# Batt_Op_Amp.net
KiCad netlist of a schematic drawn in Altium Designer
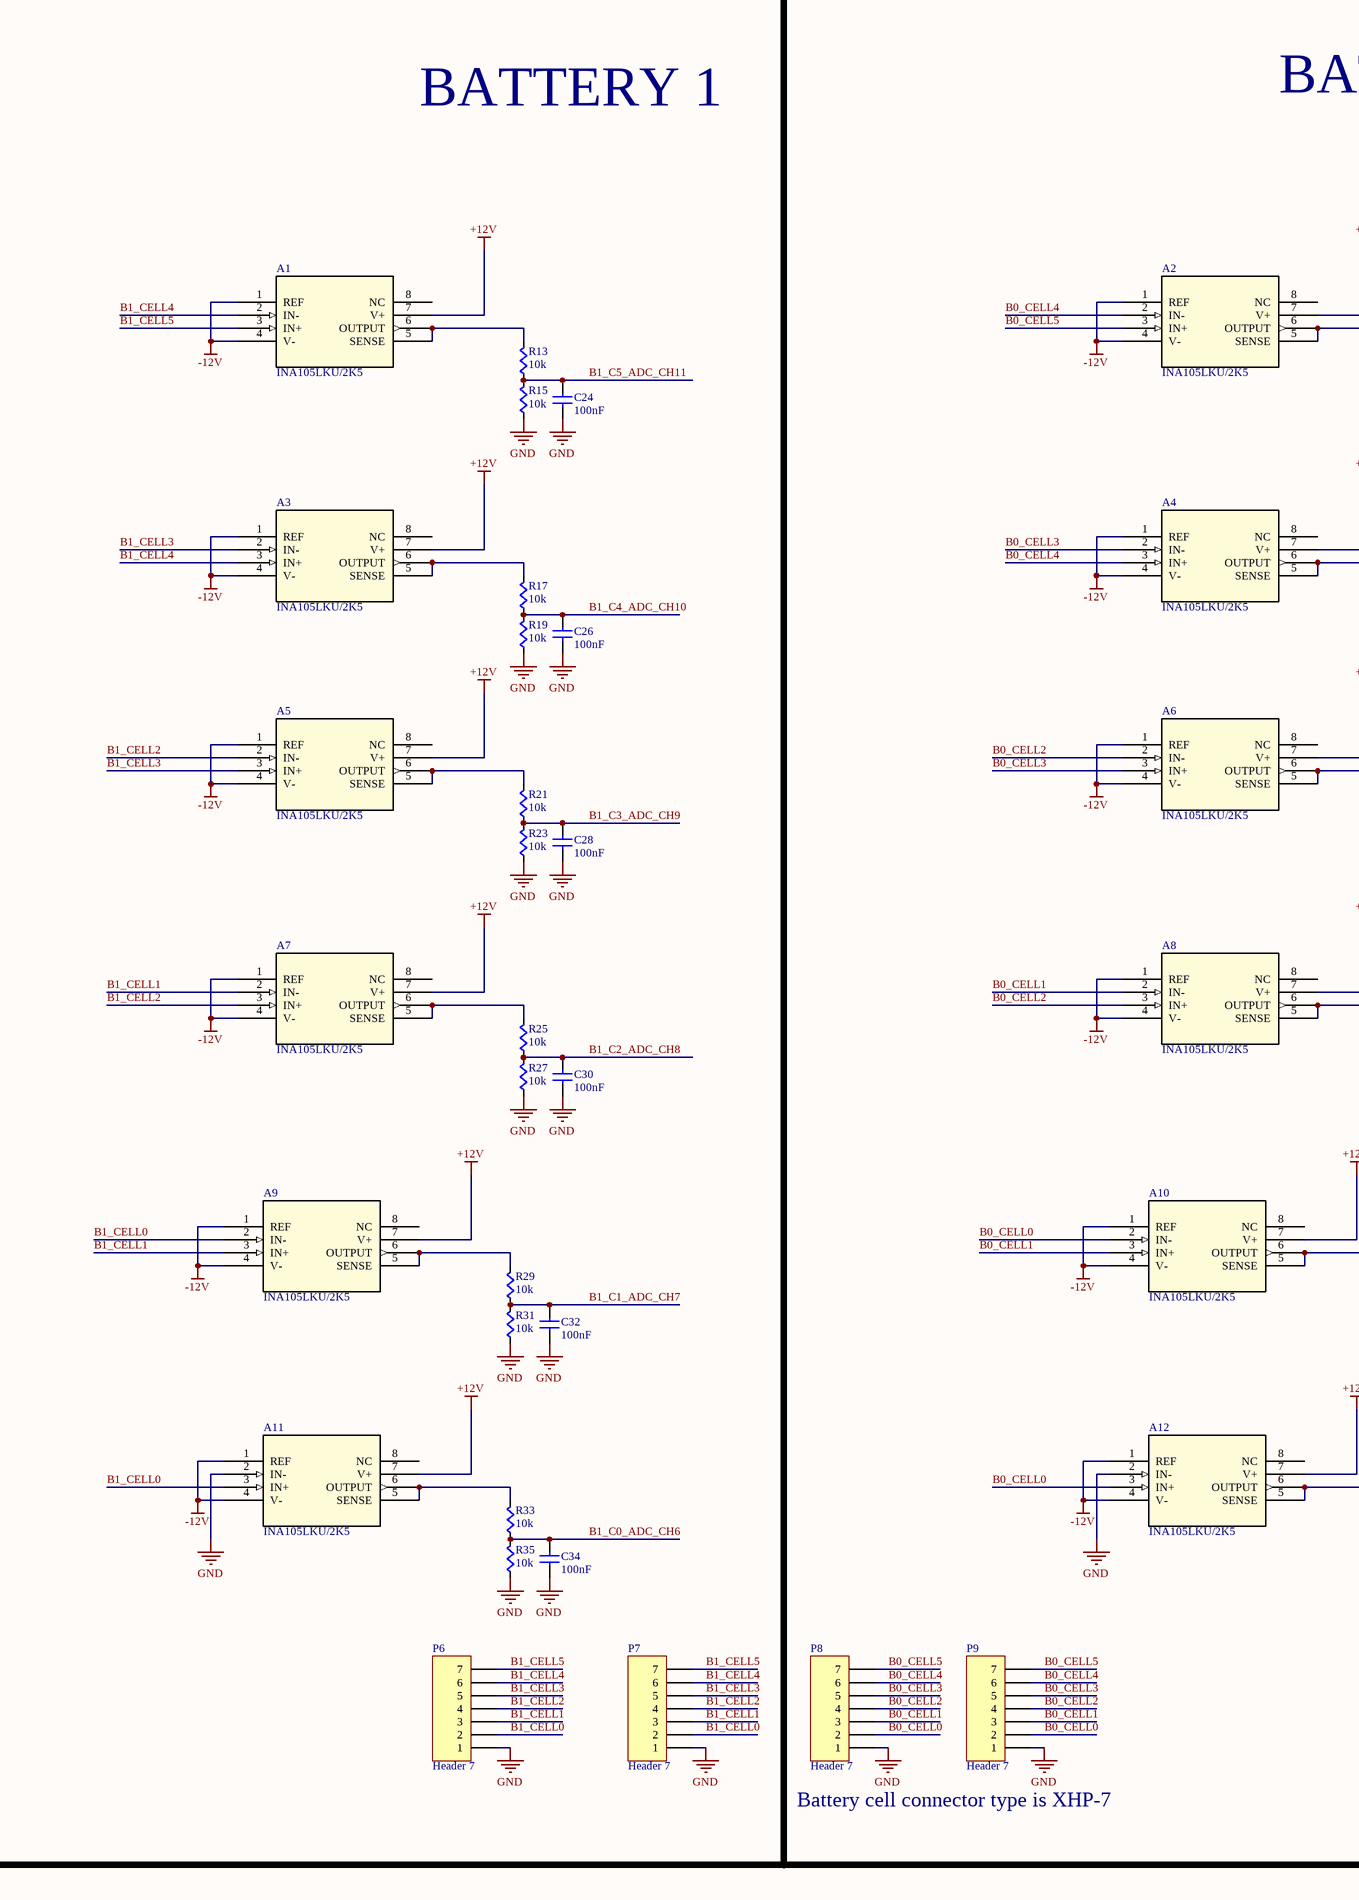
[diagram p0: Batt_Op_Amp.SchDoc, left]
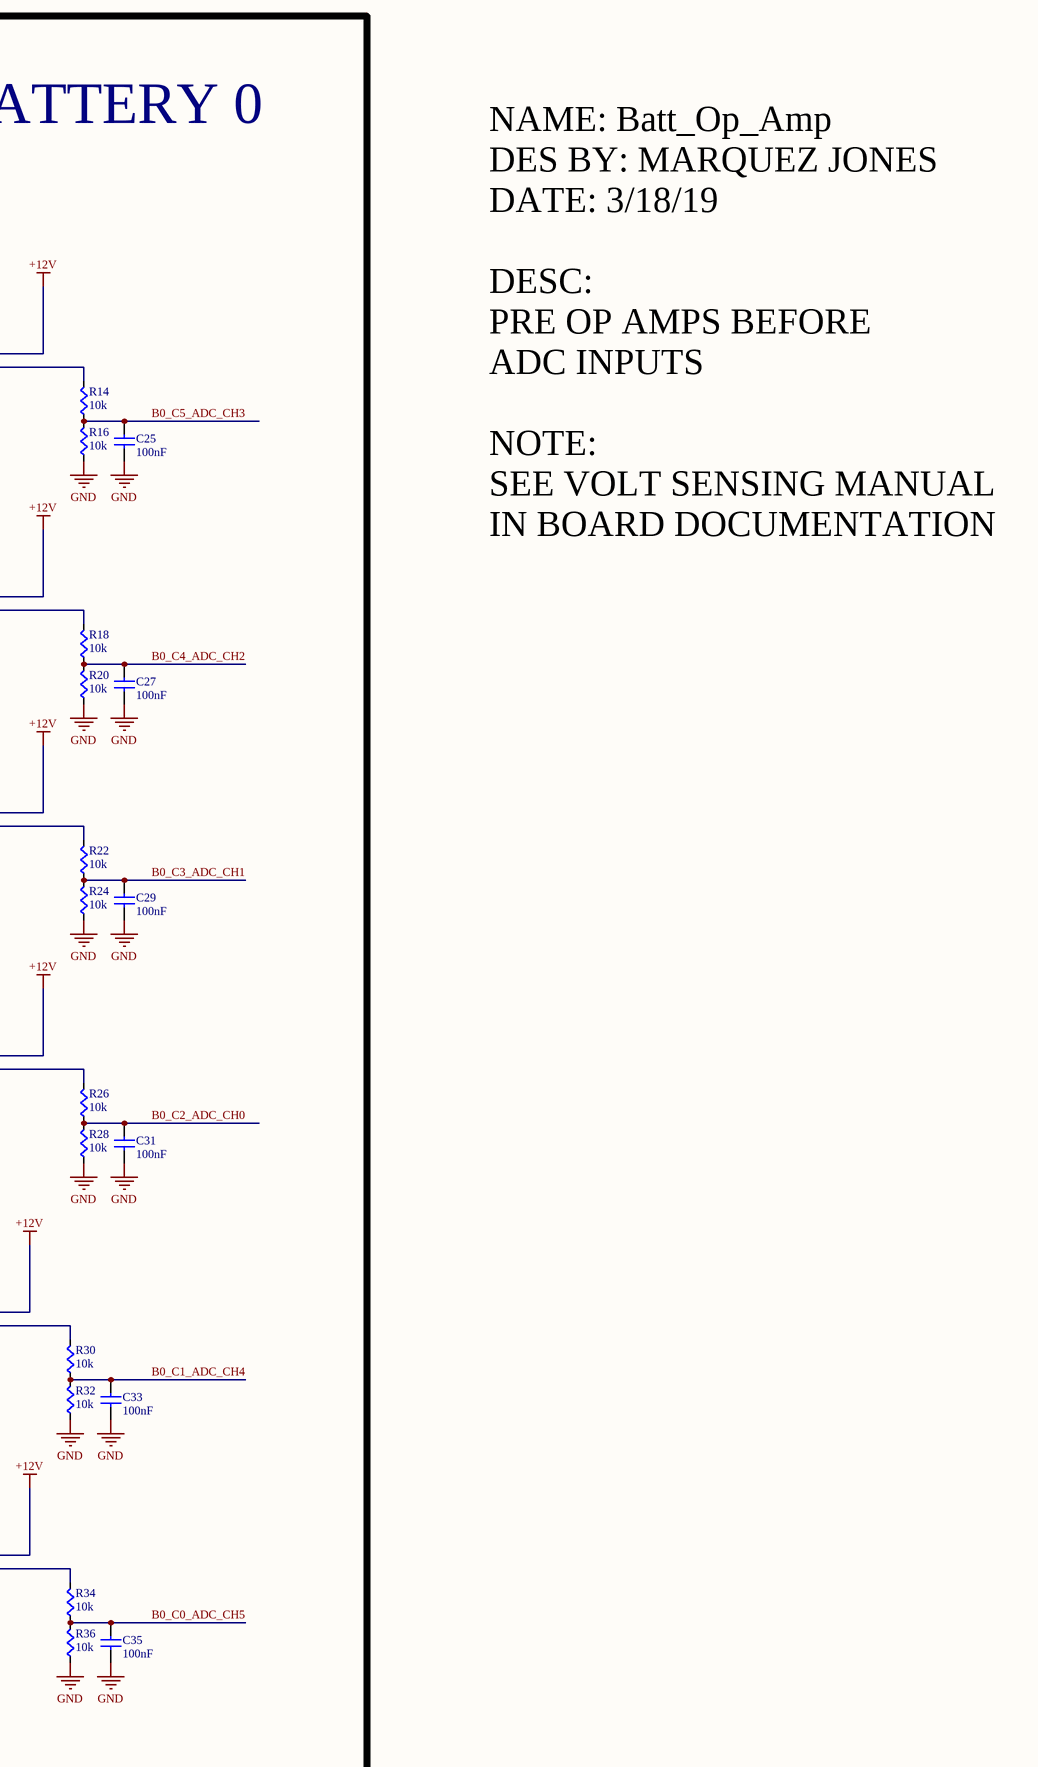
[diagram p1: Batt_Op_Amp.SchDoc, right]

(export (version "E")
  (design (tool "Eeschema 10.0.6"))
  (components
    (comp (ref "A1")
      (value "INA105LKU/2K5")
      (footprint "SOIC-8N")
      (libsource (lib "ICs") (part "INA105LKU/2K5"))
    )
    (comp (ref "A2")
      (value "INA105LKU/2K5")
      (footprint "SOIC-8N")
      (libsource (lib "ICs") (part "INA105LKU/2K5"))
    )
    (comp (ref "A3")
      (value "INA105LKU/2K5")
      (footprint "SOIC-8N")
      (libsource (lib "ICs") (part "INA105LKU/2K5"))
    )
    (comp (ref "A4")
      (value "INA105LKU/2K5")
      (footprint "SOIC-8N")
      (libsource (lib "ICs") (part "INA105LKU/2K5"))
    )
    (comp (ref "A5")
      (value "INA105LKU/2K5")
      (footprint "SOIC-8N")
      (libsource (lib "ICs") (part "INA105LKU/2K5"))
    )
    (comp (ref "A6")
      (value "INA105LKU/2K5")
      (footprint "SOIC-8N")
      (libsource (lib "ICs") (part "INA105LKU/2K5"))
    )
    (comp (ref "A7")
      (value "INA105LKU/2K5")
      (footprint "SOIC-8N")
      (libsource (lib "ICs") (part "INA105LKU/2K5"))
    )
    (comp (ref "A8")
      (value "INA105LKU/2K5")
      (footprint "SOIC-8N")
      (libsource (lib "ICs") (part "INA105LKU/2K5"))
    )
    (comp (ref "A9")
      (value "INA105LKU/2K5")
      (footprint "SOIC-8N")
      (libsource (lib "ICs") (part "INA105LKU/2K5"))
    )
    (comp (ref "A10")
      (value "INA105LKU/2K5")
      (footprint "SOIC-8N")
      (libsource (lib "ICs") (part "INA105LKU/2K5"))
    )
    (comp (ref "A11")
      (value "INA105LKU/2K5")
      (footprint "SOIC-8N")
      (libsource (lib "ICs") (part "INA105LKU/2K5"))
    )
    (comp (ref "A12")
      (value "INA105LKU/2K5")
      (footprint "SOIC-8N")
      (libsource (lib "ICs") (part "INA105LKU/2K5"))
    )
    (comp (ref "C24")
      (value "100nF")
      (footprint "CAPC0603")
      (fields (field (name "Comment") "Cap"))
      (libsource (lib "Passives") (part "Cap"))
    )
    (comp (ref "C25")
      (value "100nF")
      (footprint "CAPC0603")
      (fields (field (name "Comment") "Cap"))
      (libsource (lib "Passives") (part "Cap"))
    )
    (comp (ref "C26")
      (value "100nF")
      (footprint "CAPC0603")
      (fields (field (name "Comment") "Cap"))
      (libsource (lib "Passives") (part "Cap"))
    )
    (comp (ref "C27")
      (value "100nF")
      (footprint "CAPC0603")
      (fields (field (name "Comment") "Cap"))
      (libsource (lib "Passives") (part "Cap"))
    )
    (comp (ref "C28")
      (value "100nF")
      (footprint "CAPC0603")
      (fields (field (name "Comment") "Cap"))
      (libsource (lib "Passives") (part "Cap"))
    )
    (comp (ref "C29")
      (value "100nF")
      (footprint "CAPC0603")
      (fields (field (name "Comment") "Cap"))
      (libsource (lib "Passives") (part "Cap"))
    )
    (comp (ref "C30")
      (value "100nF")
      (footprint "CAPC0603")
      (fields (field (name "Comment") "Cap"))
      (libsource (lib "Passives") (part "Cap"))
    )
    (comp (ref "C31")
      (value "100nF")
      (footprint "CAPC0603")
      (fields (field (name "Comment") "Cap"))
      (libsource (lib "Passives") (part "Cap"))
    )
    (comp (ref "C32")
      (value "100nF")
      (footprint "CAPC0603")
      (fields (field (name "Comment") "Cap"))
      (libsource (lib "Passives") (part "Cap"))
    )
    (comp (ref "C33")
      (value "100nF")
      (footprint "CAPC0603")
      (fields (field (name "Comment") "Cap"))
      (libsource (lib "Passives") (part "Cap"))
    )
    (comp (ref "C34")
      (value "100nF")
      (footprint "CAPC0603")
      (fields (field (name "Comment") "Cap"))
      (libsource (lib "Passives") (part "Cap"))
    )
    (comp (ref "C35")
      (value "100nF")
      (footprint "CAPC0603")
      (fields (field (name "Comment") "Cap"))
      (libsource (lib "Passives") (part "Cap"))
    )
    (comp (ref "P6")
      (value "Header 7")
      (footprint "HDR1X7")
      (description "Header, 7-Pin")
      (fields (field (name "PUBLISHER") "Altium Limited"))
      (libsource (lib "Miscellaneous Connectors") (part "Header 7"))
    )
    (comp (ref "P7")
      (value "Header 7")
      (footprint "HDR1X7")
      (description "Header, 7-Pin")
      (fields (field (name "PUBLISHER") "Altium Limited"))
      (libsource (lib "Miscellaneous Connectors") (part "Header 7"))
    )
    (comp (ref "P8")
      (value "Header 7")
      (footprint "HDR1X7")
      (description "Header, 7-Pin")
      (fields (field (name "PUBLISHER") "Altium Limited"))
      (libsource (lib "Miscellaneous Connectors") (part "Header 7"))
    )
    (comp (ref "P9")
      (value "Header 7")
      (footprint "HDR1X7")
      (description "Header, 7-Pin")
      (fields (field (name "PUBLISHER") "Altium Limited"))
      (libsource (lib "Miscellaneous Connectors") (part "Header 7"))
    )
    (comp (ref "R13")
      (value "10k")
      (footprint "RES0603")
      (fields (field (name "Comment") "Res"))
      (libsource (lib "Passives") (part "Res"))
    )
    (comp (ref "R14")
      (value "10k")
      (footprint "RES0603")
      (fields (field (name "Comment") "Res"))
      (libsource (lib "Passives") (part "Res"))
    )
    (comp (ref "R15")
      (value "10k")
      (footprint "RES0603")
      (fields (field (name "Comment") "Res"))
      (libsource (lib "Passives") (part "Res"))
    )
    (comp (ref "R16")
      (value "10k")
      (footprint "RES0603")
      (fields (field (name "Comment") "Res"))
      (libsource (lib "Passives") (part "Res"))
    )
    (comp (ref "R17")
      (value "10k")
      (footprint "RES0603")
      (fields (field (name "Comment") "Res"))
      (libsource (lib "Passives") (part "Res"))
    )
    (comp (ref "R18")
      (value "10k")
      (footprint "RES0603")
      (fields (field (name "Comment") "Res"))
      (libsource (lib "Passives") (part "Res"))
    )
    (comp (ref "R19")
      (value "10k")
      (footprint "RES0603")
      (fields (field (name "Comment") "Res"))
      (libsource (lib "Passives") (part "Res"))
    )
    (comp (ref "R20")
      (value "10k")
      (footprint "RES0603")
      (fields (field (name "Comment") "Res"))
      (libsource (lib "Passives") (part "Res"))
    )
    (comp (ref "R21")
      (value "10k")
      (footprint "RES0603")
      (fields (field (name "Comment") "Res"))
      (libsource (lib "Passives") (part "Res"))
    )
    (comp (ref "R22")
      (value "10k")
      (footprint "RES0603")
      (fields (field (name "Comment") "Res"))
      (libsource (lib "Passives") (part "Res"))
    )
    (comp (ref "R23")
      (value "10k")
      (footprint "RES0603")
      (fields (field (name "Comment") "Res"))
      (libsource (lib "Passives") (part "Res"))
    )
    (comp (ref "R24")
      (value "10k")
      (footprint "RES0603")
      (fields (field (name "Comment") "Res"))
      (libsource (lib "Passives") (part "Res"))
    )
    (comp (ref "R25")
      (value "10k")
      (footprint "RES0603")
      (fields (field (name "Comment") "Res"))
      (libsource (lib "Passives") (part "Res"))
    )
    (comp (ref "R26")
      (value "10k")
      (footprint "RES0603")
      (fields (field (name "Comment") "Res"))
      (libsource (lib "Passives") (part "Res"))
    )
    (comp (ref "R27")
      (value "10k")
      (footprint "RES0603")
      (fields (field (name "Comment") "Res"))
      (libsource (lib "Passives") (part "Res"))
    )
    (comp (ref "R28")
      (value "10k")
      (footprint "RES0603")
      (fields (field (name "Comment") "Res"))
      (libsource (lib "Passives") (part "Res"))
    )
    (comp (ref "R29")
      (value "10k")
      (footprint "RES0603")
      (fields (field (name "Comment") "Res"))
      (libsource (lib "Passives") (part "Res"))
    )
    (comp (ref "R30")
      (value "10k")
      (footprint "RES0603")
      (fields (field (name "Comment") "Res"))
      (libsource (lib "Passives") (part "Res"))
    )
    (comp (ref "R31")
      (value "10k")
      (footprint "RES0603")
      (fields (field (name "Comment") "Res"))
      (libsource (lib "Passives") (part "Res"))
    )
    (comp (ref "R32")
      (value "10k")
      (footprint "RES0603")
      (fields (field (name "Comment") "Res"))
      (libsource (lib "Passives") (part "Res"))
    )
    (comp (ref "R33")
      (value "10k")
      (footprint "RES0603")
      (fields (field (name "Comment") "Res"))
      (libsource (lib "Passives") (part "Res"))
    )
    (comp (ref "R34")
      (value "10k")
      (footprint "RES0603")
      (fields (field (name "Comment") "Res"))
      (libsource (lib "Passives") (part "Res"))
    )
    (comp (ref "R35")
      (value "10k")
      (footprint "RES0603")
      (fields (field (name "Comment") "Res"))
      (libsource (lib "Passives") (part "Res"))
    )
    (comp (ref "R36")
      (value "10k")
      (footprint "RES0603")
      (fields (field (name "Comment") "Res"))
      (libsource (lib "Passives") (part "Res"))
    )
  )
  (nets
    (net (code "1") (name "+12V") (class "Default")
      (node (ref "A1") (pin "7") (pinfunction "V+_7") (pintype "power_in"))
      (node (ref "A10") (pin "7") (pinfunction "V+_7") (pintype "power_in"))
      (node (ref "A11") (pin "7") (pinfunction "V+_7") (pintype "power_in"))
      (node (ref "A12") (pin "7") (pinfunction "V+_7") (pintype "power_in"))
      (node (ref "A2") (pin "7") (pinfunction "V+_7") (pintype "power_in"))
      (node (ref "A3") (pin "7") (pinfunction "V+_7") (pintype "power_in"))
      (node (ref "A4") (pin "7") (pinfunction "V+_7") (pintype "power_in"))
      (node (ref "A5") (pin "7") (pinfunction "V+_7") (pintype "power_in"))
      (node (ref "A6") (pin "7") (pinfunction "V+_7") (pintype "power_in"))
      (node (ref "A7") (pin "7") (pinfunction "V+_7") (pintype "power_in"))
      (node (ref "A8") (pin "7") (pinfunction "V+_7") (pintype "power_in"))
      (node (ref "A9") (pin "7") (pinfunction "V+_7") (pintype "power_in"))
    )
    (net (code "2") (name "-12V") (class "Default")
      (node (ref "A1") (pin "1") (pinfunction "REF_1") (pintype "power_in"))
      (node (ref "A1") (pin "4") (pinfunction "V-_4") (pintype "power_in"))
      (node (ref "A10") (pin "1") (pinfunction "REF_1") (pintype "power_in"))
      (node (ref "A10") (pin "4") (pinfunction "V-_4") (pintype "power_in"))
      (node (ref "A11") (pin "1") (pinfunction "REF_1") (pintype "power_in"))
      (node (ref "A11") (pin "4") (pinfunction "V-_4") (pintype "power_in"))
      (node (ref "A12") (pin "1") (pinfunction "REF_1") (pintype "power_in"))
      (node (ref "A12") (pin "4") (pinfunction "V-_4") (pintype "power_in"))
      (node (ref "A2") (pin "1") (pinfunction "REF_1") (pintype "power_in"))
      (node (ref "A2") (pin "4") (pinfunction "V-_4") (pintype "power_in"))
      (node (ref "A3") (pin "1") (pinfunction "REF_1") (pintype "power_in"))
      (node (ref "A3") (pin "4") (pinfunction "V-_4") (pintype "power_in"))
      (node (ref "A4") (pin "1") (pinfunction "REF_1") (pintype "power_in"))
      (node (ref "A4") (pin "4") (pinfunction "V-_4") (pintype "power_in"))
      (node (ref "A5") (pin "1") (pinfunction "REF_1") (pintype "power_in"))
      (node (ref "A5") (pin "4") (pinfunction "V-_4") (pintype "power_in"))
      (node (ref "A6") (pin "1") (pinfunction "REF_1") (pintype "power_in"))
      (node (ref "A6") (pin "4") (pinfunction "V-_4") (pintype "power_in"))
      (node (ref "A7") (pin "1") (pinfunction "REF_1") (pintype "power_in"))
      (node (ref "A7") (pin "4") (pinfunction "V-_4") (pintype "power_in"))
      (node (ref "A8") (pin "1") (pinfunction "REF_1") (pintype "power_in"))
      (node (ref "A8") (pin "4") (pinfunction "V-_4") (pintype "power_in"))
      (node (ref "A9") (pin "1") (pinfunction "REF_1") (pintype "power_in"))
      (node (ref "A9") (pin "4") (pinfunction "V-_4") (pintype "power_in"))
    )
    (net (code "3") (name "/B0_C0_ADC_CH5") (class "Default")
      (node (ref "C35") (pin "1") (pinfunction "A_1") (pintype "passive"))
      (node (ref "R34") (pin "2") (pinfunction "B_2") (pintype "passive"))
      (node (ref "R36") (pin "1") (pinfunction "A_1") (pintype "passive"))
    )
    (net (code "4") (name "/B0_C1_ADC_CH4") (class "Default")
      (node (ref "C33") (pin "1") (pinfunction "A_1") (pintype "passive"))
      (node (ref "R30") (pin "2") (pinfunction "B_2") (pintype "passive"))
      (node (ref "R32") (pin "1") (pinfunction "A_1") (pintype "passive"))
    )
    (net (code "5") (name "/B0_C2_ADC_CH0") (class "Default")
      (node (ref "C31") (pin "1") (pinfunction "A_1") (pintype "passive"))
      (node (ref "R26") (pin "2") (pinfunction "B_2") (pintype "passive"))
      (node (ref "R28") (pin "1") (pinfunction "A_1") (pintype "passive"))
    )
    (net (code "6") (name "/B0_C3_ADC_CH1") (class "Default")
      (node (ref "C29") (pin "1") (pinfunction "A_1") (pintype "passive"))
      (node (ref "R22") (pin "2") (pinfunction "B_2") (pintype "passive"))
      (node (ref "R24") (pin "1") (pinfunction "A_1") (pintype "passive"))
    )
    (net (code "7") (name "/B0_C4_ADC_CH2") (class "Default")
      (node (ref "C27") (pin "1") (pinfunction "A_1") (pintype "passive"))
      (node (ref "R18") (pin "2") (pinfunction "B_2") (pintype "passive"))
      (node (ref "R20") (pin "1") (pinfunction "A_1") (pintype "passive"))
    )
    (net (code "8") (name "/B0_C5_ADC_CH3") (class "Default")
      (node (ref "C25") (pin "1") (pinfunction "A_1") (pintype "passive"))
      (node (ref "R14") (pin "2") (pinfunction "B_2") (pintype "passive"))
      (node (ref "R16") (pin "1") (pinfunction "A_1") (pintype "passive"))
    )
    (net (code "9") (name "/B0_CELL0") (class "Default")
      (node (ref "A10") (pin "2") (pinfunction "IN-_2") (pintype "input"))
      (node (ref "A12") (pin "3") (pinfunction "IN+_3") (pintype "input"))
      (node (ref "P8") (pin "2") (pinfunction "2_2") (pintype "passive"))
      (node (ref "P9") (pin "2") (pinfunction "2_2") (pintype "passive"))
    )
    (net (code "10") (name "/B0_CELL1") (class "Default")
      (node (ref "A10") (pin "3") (pinfunction "IN+_3") (pintype "input"))
      (node (ref "A8") (pin "2") (pinfunction "IN-_2") (pintype "input"))
      (node (ref "P8") (pin "3") (pinfunction "3_3") (pintype "passive"))
      (node (ref "P9") (pin "3") (pinfunction "3_3") (pintype "passive"))
    )
    (net (code "11") (name "/B0_CELL2") (class "Default")
      (node (ref "A6") (pin "2") (pinfunction "IN-_2") (pintype "input"))
      (node (ref "A8") (pin "3") (pinfunction "IN+_3") (pintype "input"))
      (node (ref "P8") (pin "4") (pinfunction "4_4") (pintype "passive"))
      (node (ref "P9") (pin "4") (pinfunction "4_4") (pintype "passive"))
    )
    (net (code "12") (name "/B0_CELL3") (class "Default")
      (node (ref "A4") (pin "2") (pinfunction "IN-_2") (pintype "input"))
      (node (ref "A6") (pin "3") (pinfunction "IN+_3") (pintype "input"))
      (node (ref "P8") (pin "5") (pinfunction "5_5") (pintype "passive"))
      (node (ref "P9") (pin "5") (pinfunction "5_5") (pintype "passive"))
    )
    (net (code "13") (name "/B0_CELL4") (class "Default")
      (node (ref "A2") (pin "2") (pinfunction "IN-_2") (pintype "input"))
      (node (ref "A4") (pin "3") (pinfunction "IN+_3") (pintype "input"))
      (node (ref "P8") (pin "6") (pinfunction "6_6") (pintype "passive"))
      (node (ref "P9") (pin "6") (pinfunction "6_6") (pintype "passive"))
    )
    (net (code "14") (name "/B0_CELL5") (class "Default")
      (node (ref "A2") (pin "3") (pinfunction "IN+_3") (pintype "input"))
      (node (ref "P8") (pin "7") (pinfunction "7_7") (pintype "passive"))
      (node (ref "P9") (pin "7") (pinfunction "7_7") (pintype "passive"))
    )
    (net (code "15") (name "/B1_C0_ADC_CH6") (class "Default")
      (node (ref "C34") (pin "1") (pinfunction "A_1") (pintype "passive"))
      (node (ref "R33") (pin "2") (pinfunction "B_2") (pintype "passive"))
      (node (ref "R35") (pin "1") (pinfunction "A_1") (pintype "passive"))
    )
    (net (code "16") (name "/B1_C1_ADC_CH7") (class "Default")
      (node (ref "C32") (pin "1") (pinfunction "A_1") (pintype "passive"))
      (node (ref "R29") (pin "2") (pinfunction "B_2") (pintype "passive"))
      (node (ref "R31") (pin "1") (pinfunction "A_1") (pintype "passive"))
    )
    (net (code "17") (name "/B1_C2_ADC_CH8") (class "Default")
      (node (ref "C30") (pin "1") (pinfunction "A_1") (pintype "passive"))
      (node (ref "R25") (pin "2") (pinfunction "B_2") (pintype "passive"))
      (node (ref "R27") (pin "1") (pinfunction "A_1") (pintype "passive"))
    )
    (net (code "18") (name "/B1_C3_ADC_CH9") (class "Default")
      (node (ref "C28") (pin "1") (pinfunction "A_1") (pintype "passive"))
      (node (ref "R21") (pin "2") (pinfunction "B_2") (pintype "passive"))
      (node (ref "R23") (pin "1") (pinfunction "A_1") (pintype "passive"))
    )
    (net (code "19") (name "/B1_C4_ADC_CH10") (class "Default")
      (node (ref "C26") (pin "1") (pinfunction "A_1") (pintype "passive"))
      (node (ref "R17") (pin "2") (pinfunction "B_2") (pintype "passive"))
      (node (ref "R19") (pin "1") (pinfunction "A_1") (pintype "passive"))
    )
    (net (code "20") (name "/B1_C5_ADC_CH11") (class "Default")
      (node (ref "C24") (pin "1") (pinfunction "A_1") (pintype "passive"))
      (node (ref "R13") (pin "2") (pinfunction "B_2") (pintype "passive"))
      (node (ref "R15") (pin "1") (pinfunction "A_1") (pintype "passive"))
    )
    (net (code "21") (name "/B1_CELL0") (class "Default")
      (node (ref "A11") (pin "3") (pinfunction "IN+_3") (pintype "input"))
      (node (ref "A9") (pin "2") (pinfunction "IN-_2") (pintype "input"))
      (node (ref "P6") (pin "2") (pinfunction "2_2") (pintype "passive"))
      (node (ref "P7") (pin "2") (pinfunction "2_2") (pintype "passive"))
    )
    (net (code "22") (name "/B1_CELL1") (class "Default")
      (node (ref "A7") (pin "2") (pinfunction "IN-_2") (pintype "input"))
      (node (ref "A9") (pin "3") (pinfunction "IN+_3") (pintype "input"))
      (node (ref "P6") (pin "3") (pinfunction "3_3") (pintype "passive"))
      (node (ref "P7") (pin "3") (pinfunction "3_3") (pintype "passive"))
    )
    (net (code "23") (name "/B1_CELL2") (class "Default")
      (node (ref "A5") (pin "2") (pinfunction "IN-_2") (pintype "input"))
      (node (ref "A7") (pin "3") (pinfunction "IN+_3") (pintype "input"))
      (node (ref "P6") (pin "4") (pinfunction "4_4") (pintype "passive"))
      (node (ref "P7") (pin "4") (pinfunction "4_4") (pintype "passive"))
    )
    (net (code "24") (name "/B1_CELL3") (class "Default")
      (node (ref "A3") (pin "2") (pinfunction "IN-_2") (pintype "input"))
      (node (ref "A5") (pin "3") (pinfunction "IN+_3") (pintype "input"))
      (node (ref "P6") (pin "5") (pinfunction "5_5") (pintype "passive"))
      (node (ref "P7") (pin "5") (pinfunction "5_5") (pintype "passive"))
    )
    (net (code "25") (name "/B1_CELL4") (class "Default")
      (node (ref "A1") (pin "2") (pinfunction "IN-_2") (pintype "input"))
      (node (ref "A3") (pin "3") (pinfunction "IN+_3") (pintype "input"))
      (node (ref "P6") (pin "6") (pinfunction "6_6") (pintype "passive"))
      (node (ref "P7") (pin "6") (pinfunction "6_6") (pintype "passive"))
    )
    (net (code "26") (name "/B1_CELL5") (class "Default")
      (node (ref "A1") (pin "3") (pinfunction "IN+_3") (pintype "input"))
      (node (ref "P6") (pin "7") (pinfunction "7_7") (pintype "passive"))
      (node (ref "P7") (pin "7") (pinfunction "7_7") (pintype "passive"))
    )
    (net (code "27") (name "GND") (class "Default")
      (node (ref "A11") (pin "2") (pinfunction "IN-_2") (pintype "input"))
      (node (ref "A12") (pin "2") (pinfunction "IN-_2") (pintype "input"))
      (node (ref "C24") (pin "2") (pinfunction "B_2") (pintype "passive"))
      (node (ref "C25") (pin "2") (pinfunction "B_2") (pintype "passive"))
      (node (ref "C26") (pin "2") (pinfunction "B_2") (pintype "passive"))
      (node (ref "C27") (pin "2") (pinfunction "B_2") (pintype "passive"))
      (node (ref "C28") (pin "2") (pinfunction "B_2") (pintype "passive"))
      (node (ref "C29") (pin "2") (pinfunction "B_2") (pintype "passive"))
      (node (ref "C30") (pin "2") (pinfunction "B_2") (pintype "passive"))
      (node (ref "C31") (pin "2") (pinfunction "B_2") (pintype "passive"))
      (node (ref "C32") (pin "2") (pinfunction "B_2") (pintype "passive"))
      (node (ref "C33") (pin "2") (pinfunction "B_2") (pintype "passive"))
      (node (ref "C34") (pin "2") (pinfunction "B_2") (pintype "passive"))
      (node (ref "C35") (pin "2") (pinfunction "B_2") (pintype "passive"))
      (node (ref "P6") (pin "1") (pinfunction "1_1") (pintype "passive"))
      (node (ref "P7") (pin "1") (pinfunction "1_1") (pintype "passive"))
      (node (ref "P8") (pin "1") (pinfunction "1_1") (pintype "passive"))
      (node (ref "P9") (pin "1") (pinfunction "1_1") (pintype "passive"))
      (node (ref "R15") (pin "2") (pinfunction "B_2") (pintype "passive"))
      (node (ref "R16") (pin "2") (pinfunction "B_2") (pintype "passive"))
      (node (ref "R19") (pin "2") (pinfunction "B_2") (pintype "passive"))
      (node (ref "R20") (pin "2") (pinfunction "B_2") (pintype "passive"))
      (node (ref "R23") (pin "2") (pinfunction "B_2") (pintype "passive"))
      (node (ref "R24") (pin "2") (pinfunction "B_2") (pintype "passive"))
      (node (ref "R27") (pin "2") (pinfunction "B_2") (pintype "passive"))
      (node (ref "R28") (pin "2") (pinfunction "B_2") (pintype "passive"))
      (node (ref "R31") (pin "2") (pinfunction "B_2") (pintype "passive"))
      (node (ref "R32") (pin "2") (pinfunction "B_2") (pintype "passive"))
      (node (ref "R35") (pin "2") (pinfunction "B_2") (pintype "passive"))
      (node (ref "R36") (pin "2") (pinfunction "B_2") (pintype "passive"))
    )
    (net (code "28") (name "Net-(A1-OUTPUT)") (class "Default")
      (node (ref "A1") (pin "5") (pinfunction "SENSE_5") (pintype "passive"))
      (node (ref "A1") (pin "6") (pinfunction "OUTPUT_6") (pintype "output"))
      (node (ref "R13") (pin "1") (pinfunction "A_1") (pintype "passive"))
    )
    (net (code "29") (name "Net-(A2-OUTPUT)") (class "Default")
      (node (ref "A2") (pin "5") (pinfunction "SENSE_5") (pintype "passive"))
      (node (ref "A2") (pin "6") (pinfunction "OUTPUT_6") (pintype "output"))
      (node (ref "R14") (pin "1") (pinfunction "A_1") (pintype "passive"))
    )
    (net (code "30") (name "Net-(A3-OUTPUT)") (class "Default")
      (node (ref "A3") (pin "5") (pinfunction "SENSE_5") (pintype "passive"))
      (node (ref "A3") (pin "6") (pinfunction "OUTPUT_6") (pintype "output"))
      (node (ref "R17") (pin "1") (pinfunction "A_1") (pintype "passive"))
    )
    (net (code "31") (name "Net-(A4-OUTPUT)") (class "Default")
      (node (ref "A4") (pin "5") (pinfunction "SENSE_5") (pintype "passive"))
      (node (ref "A4") (pin "6") (pinfunction "OUTPUT_6") (pintype "output"))
      (node (ref "R18") (pin "1") (pinfunction "A_1") (pintype "passive"))
    )
    (net (code "32") (name "Net-(A5-OUTPUT)") (class "Default")
      (node (ref "A5") (pin "5") (pinfunction "SENSE_5") (pintype "passive"))
      (node (ref "A5") (pin "6") (pinfunction "OUTPUT_6") (pintype "output"))
      (node (ref "R21") (pin "1") (pinfunction "A_1") (pintype "passive"))
    )
    (net (code "33") (name "Net-(A6-OUTPUT)") (class "Default")
      (node (ref "A6") (pin "5") (pinfunction "SENSE_5") (pintype "passive"))
      (node (ref "A6") (pin "6") (pinfunction "OUTPUT_6") (pintype "output"))
      (node (ref "R22") (pin "1") (pinfunction "A_1") (pintype "passive"))
    )
    (net (code "34") (name "Net-(A7-OUTPUT)") (class "Default")
      (node (ref "A7") (pin "5") (pinfunction "SENSE_5") (pintype "passive"))
      (node (ref "A7") (pin "6") (pinfunction "OUTPUT_6") (pintype "output"))
      (node (ref "R25") (pin "1") (pinfunction "A_1") (pintype "passive"))
    )
    (net (code "35") (name "Net-(A8-OUTPUT)") (class "Default")
      (node (ref "A8") (pin "5") (pinfunction "SENSE_5") (pintype "passive"))
      (node (ref "A8") (pin "6") (pinfunction "OUTPUT_6") (pintype "output"))
      (node (ref "R26") (pin "1") (pinfunction "A_1") (pintype "passive"))
    )
    (net (code "36") (name "Net-(A9-OUTPUT)") (class "Default")
      (node (ref "A9") (pin "5") (pinfunction "SENSE_5") (pintype "passive"))
      (node (ref "A9") (pin "6") (pinfunction "OUTPUT_6") (pintype "output"))
      (node (ref "R29") (pin "1") (pinfunction "A_1") (pintype "passive"))
    )
    (net (code "37") (name "Net-(A10-OUTPUT)") (class "Default")
      (node (ref "A10") (pin "5") (pinfunction "SENSE_5") (pintype "passive"))
      (node (ref "A10") (pin "6") (pinfunction "OUTPUT_6") (pintype "output"))
      (node (ref "R30") (pin "1") (pinfunction "A_1") (pintype "passive"))
    )
    (net (code "38") (name "Net-(A11-OUTPUT)") (class "Default")
      (node (ref "A11") (pin "5") (pinfunction "SENSE_5") (pintype "passive"))
      (node (ref "A11") (pin "6") (pinfunction "OUTPUT_6") (pintype "output"))
      (node (ref "R33") (pin "1") (pinfunction "A_1") (pintype "passive"))
    )
    (net (code "39") (name "Net-(A12-OUTPUT)") (class "Default")
      (node (ref "A12") (pin "5") (pinfunction "SENSE_5") (pintype "passive"))
      (node (ref "A12") (pin "6") (pinfunction "OUTPUT_6") (pintype "output"))
      (node (ref "R34") (pin "1") (pinfunction "A_1") (pintype "passive"))
    )
    (net (code "40") (name "unconnected-(A1-NC-Pad8)") (class "Default")
      (node (ref "A1") (pin "8") (pinfunction "NC_8") (pintype "passive"))
    )
    (net (code "41") (name "unconnected-(A2-NC-Pad8)") (class "Default")
      (node (ref "A2") (pin "8") (pinfunction "NC_8") (pintype "passive"))
    )
    (net (code "42") (name "unconnected-(A3-NC-Pad8)") (class "Default")
      (node (ref "A3") (pin "8") (pinfunction "NC_8") (pintype "passive"))
    )
    (net (code "43") (name "unconnected-(A4-NC-Pad8)") (class "Default")
      (node (ref "A4") (pin "8") (pinfunction "NC_8") (pintype "passive"))
    )
    (net (code "44") (name "unconnected-(A5-NC-Pad8)") (class "Default")
      (node (ref "A5") (pin "8") (pinfunction "NC_8") (pintype "passive"))
    )
    (net (code "45") (name "unconnected-(A6-NC-Pad8)") (class "Default")
      (node (ref "A6") (pin "8") (pinfunction "NC_8") (pintype "passive"))
    )
    (net (code "46") (name "unconnected-(A7-NC-Pad8)") (class "Default")
      (node (ref "A7") (pin "8") (pinfunction "NC_8") (pintype "passive"))
    )
    (net (code "47") (name "unconnected-(A8-NC-Pad8)") (class "Default")
      (node (ref "A8") (pin "8") (pinfunction "NC_8") (pintype "passive"))
    )
    (net (code "48") (name "unconnected-(A9-NC-Pad8)") (class "Default")
      (node (ref "A9") (pin "8") (pinfunction "NC_8") (pintype "passive"))
    )
    (net (code "49") (name "unconnected-(A10-NC-Pad8)") (class "Default")
      (node (ref "A10") (pin "8") (pinfunction "NC_8") (pintype "passive"))
    )
    (net (code "50") (name "unconnected-(A11-NC-Pad8)") (class "Default")
      (node (ref "A11") (pin "8") (pinfunction "NC_8") (pintype "passive"))
    )
    (net (code "51") (name "unconnected-(A12-NC-Pad8)") (class "Default")
      (node (ref "A12") (pin "8") (pinfunction "NC_8") (pintype "passive"))
    )
  )
)
